# HumidityMetter_v2.net
KiCad netlist of a schematic drawn in EAGLE
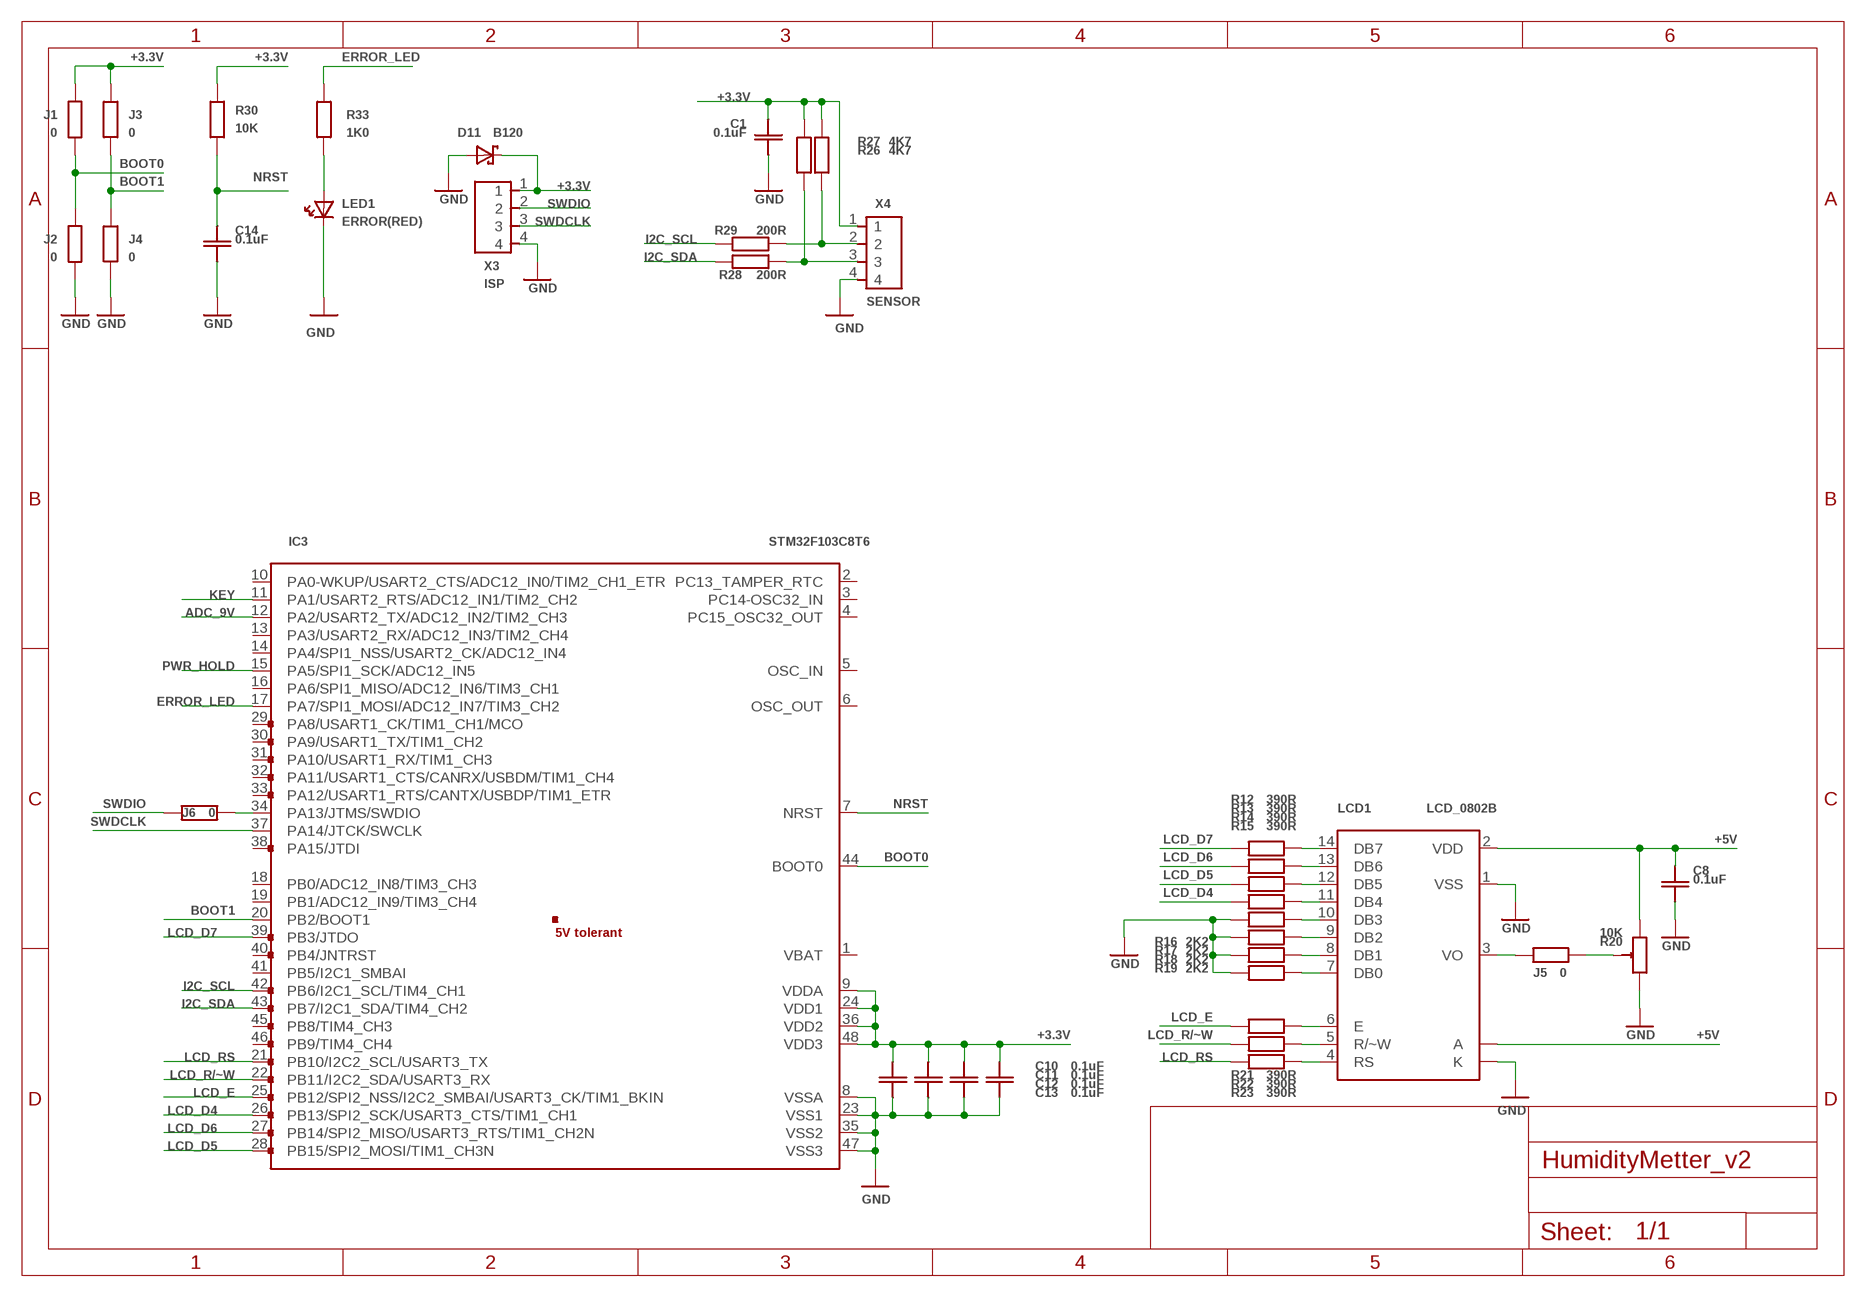
[diagram p0: schematic, sheet 1, part 1 of 2]
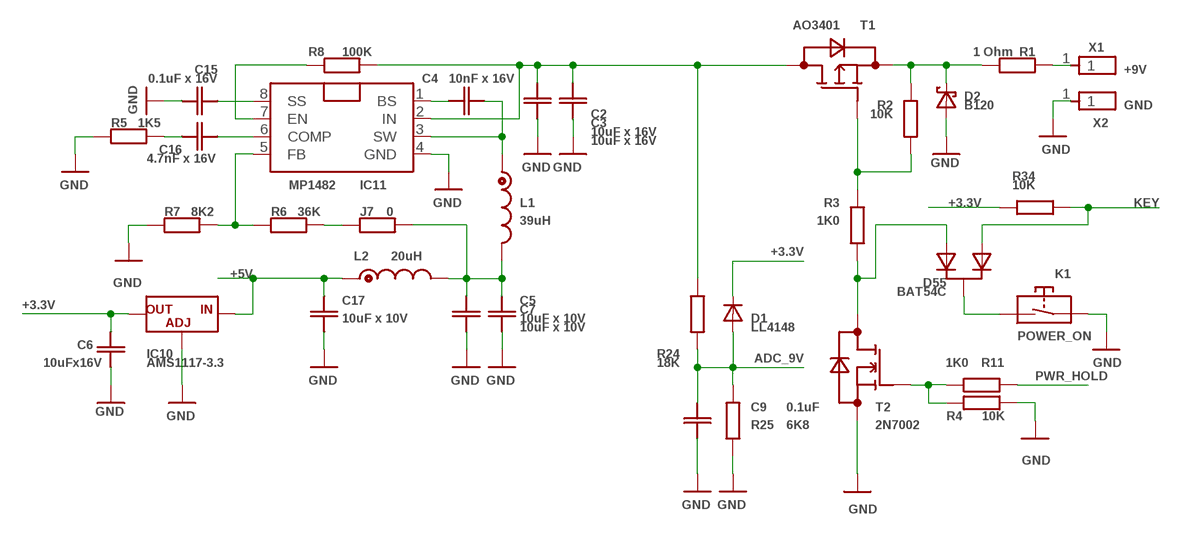
[diagram p1: schematic, sheet 1, part 2 of 2]

(export (version "E")
  (design (tool "Eeschema 10.0.6"))
  (components
    (comp (ref "C1")
      (value "0.1uF")
      (footprint "eagle-import:RSMD_0603")
      (libsource (lib "eagle-import") (part "CSMD_0603"))
    )
    (comp (ref "C2")
      (value "10uF x 16V")
      (footprint "eagle-import:RSMD_1206")
      (libsource (lib "eagle-import") (part "CSMD_1206"))
    )
    (comp (ref "C3")
      (value "10uF x 16V")
      (footprint "eagle-import:RSMD_1206")
      (libsource (lib "eagle-import") (part "CSMD_1206"))
    )
    (comp (ref "C4")
      (value "10nF x 16V")
      (footprint "eagle-import:RSMD_0603")
      (libsource (lib "eagle-import") (part "CSMD_0603"))
    )
    (comp (ref "C5")
      (value "10uF x 10V")
      (footprint "eagle-import:RSMD_1206")
      (libsource (lib "eagle-import") (part "CSMD_1206"))
    )
    (comp (ref "C6")
      (value "10uFx16V")
      (footprint "eagle-import:RSMD_1206")
      (libsource (lib "eagle-import") (part "CSMD_1206"))
    )
    (comp (ref "C7")
      (value "10uF x 10V")
      (footprint "eagle-import:RSMD_1206")
      (libsource (lib "eagle-import") (part "CSMD_1206"))
    )
    (comp (ref "C8")
      (value "0.1uF")
      (footprint "eagle-import:RSMD_0603")
      (libsource (lib "eagle-import") (part "CSMD_0603"))
    )
    (comp (ref "C9")
      (value "0.1uF")
      (footprint "eagle-import:RSMD_0603")
      (libsource (lib "eagle-import") (part "CSMD_0603"))
    )
    (comp (ref "C10")
      (value "0.1uF")
      (footprint "eagle-import:RSMD_0603")
      (libsource (lib "eagle-import") (part "CSMD_0603"))
    )
    (comp (ref "C11")
      (value "0.1uF")
      (footprint "eagle-import:RSMD_0603")
      (libsource (lib "eagle-import") (part "CSMD_0603"))
    )
    (comp (ref "C12")
      (value "0.1uF")
      (footprint "eagle-import:RSMD_0603")
      (libsource (lib "eagle-import") (part "CSMD_0603"))
    )
    (comp (ref "C13")
      (value "0.1uF")
      (footprint "eagle-import:RSMD_0603")
      (libsource (lib "eagle-import") (part "CSMD_0603"))
    )
    (comp (ref "C14")
      (value "0.1uF")
      (footprint "eagle-import:RSMD_0603")
      (libsource (lib "eagle-import") (part "CSMD_0603"))
    )
    (comp (ref "C15")
      (value "0.1uF x 16V")
      (footprint "eagle-import:RSMD_0603")
      (libsource (lib "eagle-import") (part "CSMD_0603"))
    )
    (comp (ref "C16")
      (value "4.7nF x 16V")
      (footprint "eagle-import:RSMD_0603")
      (libsource (lib "eagle-import") (part "CSMD_0603"))
    )
    (comp (ref "C17")
      (value "10uF x 10V")
      (footprint "eagle-import:RSMD_1206")
      (libsource (lib "eagle-import") (part "CSMD_1206"))
    )
    (comp (ref "D1")
      (value "LL4148")
      (footprint "eagle-import:SOD-80")
      (libsource (lib "eagle-import") (part "LL4147SOD-80"))
    )
    (comp (ref "D2")
      (value "B120")
      (footprint "eagle-import:DO-214AC")
      (libsource (lib "eagle-import") (part "B120(DO-214AC)"))
    )
    (comp (ref "D11")
      (value "B120")
      (footprint "eagle-import:DO-214AC")
      (libsource (lib "eagle-import") (part "B120(DO-214AC)"))
    )
    (comp (ref "D55")
      (value "BAT54C")
      (footprint "eagle-import:SOT23_SMALL_PADS")
      (libsource (lib "eagle-import") (part "BAT54C(SOT23)"))
    )
    (comp (ref "IC3")
      (value "STM32F103C8T6")
      (footprint "eagle-import:LQFP48")
      (libsource (lib "eagle-import") (part "STM32F103C8T6(LQFP48)(LQFP48)"))
    )
    (comp (ref "IC10")
      (value "AMS1117-3.3")
      (footprint "eagle-import:SOT223(WAVE_SOLDERING)")
      (libsource (lib "eagle-import") (part "AMS1117SOT223_WS"))
    )
    (comp (ref "IC11")
      (value "MP1482")
      (footprint "eagle-import:SOIC8")
      (libsource (lib "eagle-import") (part "MP1482(SO-8)"))
    )
    (comp (ref "J1")
      (value "0")
      (footprint "eagle-import:RSMD_0603")
      (libsource (lib "eagle-import") (part "RSMD_0603"))
    )
    (comp (ref "J2")
      (value "0")
      (footprint "eagle-import:RSMD_0603")
      (libsource (lib "eagle-import") (part "RSMD_0603"))
    )
    (comp (ref "J3")
      (value "0")
      (footprint "eagle-import:RSMD_0603")
      (libsource (lib "eagle-import") (part "RSMD_0603"))
    )
    (comp (ref "J4")
      (value "0")
      (footprint "eagle-import:RSMD_0603")
      (libsource (lib "eagle-import") (part "RSMD_0603"))
    )
    (comp (ref "J5")
      (value "0")
      (footprint "eagle-import:RSMD_1206_BIG_GAP")
      (libsource (lib "eagle-import") (part "RSMD_1206_BIG_GAP"))
    )
    (comp (ref "J6")
      (value "0")
      (footprint "eagle-import:RSMD_0805")
      (libsource (lib "eagle-import") (part "RSMD_0805"))
    )
    (comp (ref "J7")
      (value "0")
      (footprint "eagle-import:RSMD_1206_BIG_GAP")
      (libsource (lib "eagle-import") (part "RSMD_1206_BIG_GAP"))
    )
    (comp (ref "K1")
      (value "POWER_ON")
      (footprint "eagle-import:KEY_7X4.5")
      (libsource (lib "eagle-import") (part "KEY(7X4.5)"))
    )
    (comp (ref "L1")
      (value "39uH")
      (footprint "eagle-import:COIL_7MM")
      (libsource (lib "eagle-import") (part "L(7MM)"))
    )
    (comp (ref "L2")
      (value "20uH")
      (footprint "eagle-import:RSMD_1206")
      (libsource (lib "eagle-import") (part "L(1206)"))
    )
    (comp (ref "LCD1")
      (value "LCD_0802B")
      (footprint "eagle-import:LCD_0802B_2SCREW(CHINA_CLONE)")
      (libsource (lib "eagle-import") (part "LCD_0802BLCD_0802B_2SCREW(CHINA_CLONE)"))
    )
    (comp (ref "LED1")
      (value "ERROR(RED)")
      (footprint "eagle-import:LED_0805")
      (libsource (lib "eagle-import") (part "LED3MM(SMD0805)"))
    )
    (comp (ref "R1")
      (value "1 Ohm")
      (footprint "eagle-import:RSMD_1206")
      (libsource (lib "eagle-import") (part "RSMD_1206"))
    )
    (comp (ref "R2")
      (value "10K")
      (footprint "eagle-import:RSMD_0603")
      (libsource (lib "eagle-import") (part "RSMD_0603"))
    )
    (comp (ref "R3")
      (value "1K0")
      (footprint "eagle-import:RSMD_0603")
      (libsource (lib "eagle-import") (part "RSMD_0603"))
    )
    (comp (ref "R4")
      (value "10K")
      (footprint "eagle-import:RSMD_0603")
      (libsource (lib "eagle-import") (part "RSMD_0603"))
    )
    (comp (ref "R5")
      (value "1K5")
      (footprint "eagle-import:RSMD_0603")
      (libsource (lib "eagle-import") (part "RSMD_0603"))
    )
    (comp (ref "R6")
      (value "36K")
      (footprint "eagle-import:RSMD_0603")
      (libsource (lib "eagle-import") (part "RSMD_0603"))
    )
    (comp (ref "R7")
      (value "8K2")
      (footprint "eagle-import:RSMD_0603")
      (libsource (lib "eagle-import") (part "RSMD_0603"))
    )
    (comp (ref "R8")
      (value "100K")
      (footprint "eagle-import:RSMD_0603")
      (libsource (lib "eagle-import") (part "RSMD_0603"))
    )
    (comp (ref "R11")
      (value "1K0")
      (footprint "eagle-import:RSMD_0603")
      (libsource (lib "eagle-import") (part "RSMD_0603"))
    )
    (comp (ref "R12")
      (value "390R")
      (footprint "eagle-import:RSMD_0805")
      (libsource (lib "eagle-import") (part "RSMD_0805"))
    )
    (comp (ref "R13")
      (value "390R")
      (footprint "eagle-import:RSMD_0603")
      (libsource (lib "eagle-import") (part "RSMD_0603"))
    )
    (comp (ref "R14")
      (value "390R")
      (footprint "eagle-import:RSMD_0603")
      (libsource (lib "eagle-import") (part "RSMD_0603"))
    )
    (comp (ref "R15")
      (value "390R")
      (footprint "eagle-import:RSMD_0603")
      (libsource (lib "eagle-import") (part "RSMD_0603"))
    )
    (comp (ref "R16")
      (value "2K2")
      (footprint "eagle-import:RSMD_0603")
      (libsource (lib "eagle-import") (part "RSMD_0603"))
    )
    (comp (ref "R17")
      (value "2K2")
      (footprint "eagle-import:RSMD_0603")
      (libsource (lib "eagle-import") (part "RSMD_0603"))
    )
    (comp (ref "R18")
      (value "2K2")
      (footprint "eagle-import:RSMD_0603")
      (libsource (lib "eagle-import") (part "RSMD_0603"))
    )
    (comp (ref "R19")
      (value "2K2")
      (footprint "eagle-import:RSMD_0603")
      (libsource (lib "eagle-import") (part "RSMD_0603"))
    )
    (comp (ref "R20")
      (value "10K")
      (footprint "eagle-import:R_ADJ_HOR")
      (libsource (lib "eagle-import") (part "R_ADJHOR_7X7MM"))
    )
    (comp (ref "R21")
      (value "390R")
      (footprint "eagle-import:RSMD_0603")
      (libsource (lib "eagle-import") (part "RSMD_0603"))
    )
    (comp (ref "R22")
      (value "390R")
      (footprint "eagle-import:RSMD_0603")
      (libsource (lib "eagle-import") (part "RSMD_0603"))
    )
    (comp (ref "R23")
      (value "390R")
      (footprint "eagle-import:RSMD_0603")
      (libsource (lib "eagle-import") (part "RSMD_0603"))
    )
    (comp (ref "R24")
      (value "18K")
      (footprint "eagle-import:RSMD_0603")
      (libsource (lib "eagle-import") (part "RSMD_0603"))
    )
    (comp (ref "R25")
      (value "6K8")
      (footprint "eagle-import:RSMD_0603")
      (libsource (lib "eagle-import") (part "RSMD_0603"))
    )
    (comp (ref "R26")
      (value "4K7")
      (footprint "eagle-import:RSMD_0603")
      (libsource (lib "eagle-import") (part "RSMD_0603"))
    )
    (comp (ref "R27")
      (value "4K7")
      (footprint "eagle-import:RSMD_0603")
      (libsource (lib "eagle-import") (part "RSMD_0603"))
    )
    (comp (ref "R28")
      (value "200R")
      (footprint "eagle-import:RSMD_0603")
      (libsource (lib "eagle-import") (part "RSMD_0603"))
    )
    (comp (ref "R29")
      (value "200R")
      (footprint "eagle-import:RSMD_0603")
      (libsource (lib "eagle-import") (part "RSMD_0603"))
    )
    (comp (ref "R30")
      (value "10K")
      (footprint "eagle-import:RSMD_0603")
      (libsource (lib "eagle-import") (part "RSMD_0603"))
    )
    (comp (ref "R33")
      (value "1K0")
      (footprint "eagle-import:RSMD_0603")
      (libsource (lib "eagle-import") (part "RSMD_0603"))
    )
    (comp (ref "R34")
      (value "10K")
      (footprint "eagle-import:RSMD_0603")
      (libsource (lib "eagle-import") (part "RSMD_0603"))
    )
    (comp (ref "T1")
      (value "AO3401")
      (footprint "eagle-import:SOT23")
      (libsource (lib "eagle-import") (part "BSS84(SOT23)"))
    )
    (comp (ref "T2")
      (value "2N7002")
      (footprint "eagle-import:SOT23_SMALL_PADS")
      (libsource (lib "eagle-import") (part "2N7002SOT23_SMALL_PADS"))
    )
    (comp (ref "X1")
      (value "+9V")
      (footprint "eagle-import:PIN1X1_3.5MM_PWR")
      (libsource (lib "eagle-import") (part "PIN1X13.5MM_PWR"))
    )
    (comp (ref "X2")
      (value "GND")
      (footprint "eagle-import:PIN1X1_3.5MM_PWR")
      (libsource (lib "eagle-import") (part "PIN1X13.5MM_PWR"))
    )
    (comp (ref "X3")
      (value "ISP")
      (footprint "eagle-import:PIN4X1_2.54MM")
      (libsource (lib "eagle-import") (part "PIN4X1(2.54MM)"))
    )
    (comp (ref "X4")
      (value "SENSOR")
      (footprint "eagle-import:JST_XH2.5MM_4PIN")
      (libsource (lib "eagle-import") (part "PIN4X1(JST_XH2.5)"))
    )
  )
  (nets
    (net (code "1") (name "/+3.3V") (class "Default")
      (node (ref "C1") (pin "PAD_1") (pinfunction "PIN1_PAD_1") (pintype "bidirectional"))
      (node (ref "C10") (pin "PAD_1") (pinfunction "PIN1_PAD_1") (pintype "bidirectional"))
      (node (ref "C11") (pin "PAD_1") (pinfunction "PIN1_PAD_1") (pintype "bidirectional"))
      (node (ref "C12") (pin "PAD_1") (pinfunction "PIN1_PAD_1") (pintype "bidirectional"))
      (node (ref "C13") (pin "PAD_1") (pinfunction "PIN1_PAD_1") (pintype "bidirectional"))
      (node (ref "C6") (pin "PAD_1") (pinfunction "PIN1_PAD_1") (pintype "bidirectional"))
      (node (ref "D1") (pin "CATHODE") (pinfunction "CATHODE_CATHODE") (pintype "passive"))
      (node (ref "D11") (pin "CATHODE") (pinfunction "CATHODE_CATHODE") (pintype "passive"))
      (node (ref "IC10") (pin "2") (pinfunction "OUT_2") (pintype "output"))
      (node (ref "IC10") (pin "4") (pinfunction "OUT_4") (pintype "output"))
      (node (ref "IC3") (pin "24") (pinfunction "VDD1_24") (pintype "bidirectional"))
      (node (ref "IC3") (pin "36") (pinfunction "VDD2_36") (pintype "bidirectional"))
      (node (ref "IC3") (pin "48") (pinfunction "VDD3_48") (pintype "bidirectional"))
      (node (ref "IC3") (pin "9") (pinfunction "VDDA_9") (pintype "bidirectional"))
      (node (ref "J1") (pin "PAD_0") (pinfunction "PIN0_PAD_0") (pintype "passive"))
      (node (ref "J3") (pin "PAD_0") (pinfunction "PIN0_PAD_0") (pintype "passive"))
      (node (ref "R26") (pin "PAD_0") (pinfunction "PIN0_PAD_0") (pintype "passive"))
      (node (ref "R27") (pin "PAD_0") (pinfunction "PIN0_PAD_0") (pintype "passive"))
      (node (ref "R30") (pin "PAD_0") (pinfunction "PIN0_PAD_0") (pintype "passive"))
      (node (ref "R34") (pin "PAD_0") (pinfunction "PIN0_PAD_0") (pintype "passive"))
      (node (ref "X3") (pin "1") (pinfunction "1_1") (pintype "bidirectional"))
      (node (ref "X4") (pin "1") (pinfunction "1_1") (pintype "bidirectional"))
    )
    (net (code "2") (name "/+5V") (class "Default")
      (node (ref "C17") (pin "PAD_1") (pinfunction "PIN1_PAD_1") (pintype "bidirectional"))
      (node (ref "C8") (pin "PAD_1") (pinfunction "PIN1_PAD_1") (pintype "bidirectional"))
      (node (ref "IC10") (pin "3") (pinfunction "IN_3") (pintype "input"))
      (node (ref "L2") (pin "PAD_1") (pinfunction "START_PAD_1") (pintype "bidirectional"))
      (node (ref "LCD1") (pin "2") (pinfunction "VDD_2") (pintype "bidirectional"))
      (node (ref "LCD1") (pin "A") (pinfunction "A_A") (pintype "bidirectional"))
      (node (ref "R20") (pin "1") (pinfunction "END_A_1") (pintype "passive"))
    )
    (net (code "3") (name "/ADC_9V") (class "Default")
      (node (ref "C9") (pin "PAD_1") (pinfunction "PIN1_PAD_1") (pintype "bidirectional"))
      (node (ref "D1") (pin "ANODE") (pinfunction "ANODE_ANODE") (pintype "passive"))
      (node (ref "IC3") (pin "12") (pinfunction "PA2/USART2_TX/ADC12_IN2/TIM2_CH3_12") (pintype "bidirectional"))
      (node (ref "R24") (pin "PAD_1") (pinfunction "PIN1_PAD_1") (pintype "passive"))
      (node (ref "R25") (pin "PAD_0") (pinfunction "PIN0_PAD_0") (pintype "passive"))
    )
    (net (code "4") (name "/BOOT0") (class "Default")
      (node (ref "IC3") (pin "44") (pinfunction "BOOT0_44") (pintype "bidirectional"))
      (node (ref "J1") (pin "PAD_1") (pinfunction "PIN1_PAD_1") (pintype "passive"))
      (node (ref "J2") (pin "PAD_0") (pinfunction "PIN0_PAD_0") (pintype "passive"))
    )
    (net (code "5") (name "/BOOT1") (class "Default")
      (node (ref "IC3") (pin "20") (pinfunction "PB2/BOOT1_20") (pintype "bidirectional"))
      (node (ref "J3") (pin "PAD_1") (pinfunction "PIN1_PAD_1") (pintype "passive"))
      (node (ref "J4") (pin "PAD_0") (pinfunction "PIN0_PAD_0") (pintype "passive"))
    )
    (net (code "6") (name "/ERROR_LED") (class "Default")
      (node (ref "IC3") (pin "17") (pinfunction "PA7/SPI1_MOSI/ADC12_IN7/TIM3_CH2_17") (pintype "bidirectional"))
      (node (ref "R33") (pin "PAD_0") (pinfunction "PIN0_PAD_0") (pintype "passive"))
    )
    (net (code "7") (name "/I2C_SCL") (class "Default")
      (node (ref "IC3") (pin "42") (pinfunction "PB6/I2C1_SCL/TIM4_CH1_42") (pintype "bidirectional"))
      (node (ref "R29") (pin "PAD_0") (pinfunction "PIN0_PAD_0") (pintype "passive"))
    )
    (net (code "8") (name "/I2C_SDA") (class "Default")
      (node (ref "IC3") (pin "43") (pinfunction "PB7/I2C1_SDA/TIM4_CH2_43") (pintype "bidirectional"))
      (node (ref "R28") (pin "PAD_0") (pinfunction "PIN0_PAD_0") (pintype "passive"))
    )
    (net (code "9") (name "/KEY") (class "Default")
      (node (ref "D55") (pin "2") (pinfunction "ANODE2_2") (pintype "passive"))
      (node (ref "IC3") (pin "11") (pinfunction "PA1/USART2_RTS/ADC12_IN1/TIM2_CH2_11") (pintype "bidirectional"))
      (node (ref "R34") (pin "PAD_1") (pinfunction "PIN1_PAD_1") (pintype "passive"))
    )
    (net (code "10") (name "/LCD_D4") (class "Default")
      (node (ref "IC3") (pin "26") (pinfunction "PB13/SPI2_SCK/USART3_CTS/TIM1_CH1_26") (pintype "bidirectional"))
      (node (ref "R15") (pin "PAD_1") (pinfunction "PIN1_PAD_1") (pintype "passive"))
    )
    (net (code "11") (name "/LCD_D5") (class "Default")
      (node (ref "IC3") (pin "28") (pinfunction "PB15/SPI2_MOSI/TIM1_CH3N_28") (pintype "bidirectional"))
      (node (ref "R14") (pin "PAD_1") (pinfunction "PIN1_PAD_1") (pintype "passive"))
    )
    (net (code "12") (name "/LCD_D6") (class "Default")
      (node (ref "IC3") (pin "27") (pinfunction "PB14/SPI2_MISO/USART3_RTS/TIM1_CH2N_27") (pintype "bidirectional"))
      (node (ref "R13") (pin "PAD_1") (pinfunction "PIN1_PAD_1") (pintype "passive"))
    )
    (net (code "13") (name "/LCD_D7") (class "Default")
      (node (ref "IC3") (pin "39") (pinfunction "PB3/JTDO_39") (pintype "bidirectional"))
      (node (ref "R12") (pin "PAD_1") (pinfunction "PIN1_PAD_1") (pintype "passive"))
    )
    (net (code "14") (name "/LCD_E") (class "Default")
      (node (ref "IC3") (pin "25") (pinfunction "PB12/SPI2_NSS/I2C2_SMBAI/USART3_CK/TIM1_BKIN_25") (pintype "bidirectional"))
      (node (ref "R21") (pin "PAD_1") (pinfunction "PIN1_PAD_1") (pintype "passive"))
    )
    (net (code "15") (name "/LCD_RS") (class "Default")
      (node (ref "IC3") (pin "21") (pinfunction "PB10/I2C2_SCL/USART3_TX_21") (pintype "bidirectional"))
      (node (ref "R23") (pin "PAD_1") (pinfunction "PIN1_PAD_1") (pintype "passive"))
    )
    (net (code "16") (name "/LCD_R{slash}~{W}") (class "Default")
      (node (ref "IC3") (pin "22") (pinfunction "PB11/I2C2_SDA/USART3_RX_22") (pintype "bidirectional"))
      (node (ref "R22") (pin "PAD_1") (pinfunction "PIN1_PAD_1") (pintype "passive"))
    )
    (net (code "17") (name "/NRST") (class "Default")
      (node (ref "C14") (pin "PAD_1") (pinfunction "PIN1_PAD_1") (pintype "bidirectional"))
      (node (ref "IC3") (pin "7") (pinfunction "NRST_7") (pintype "bidirectional"))
      (node (ref "R30") (pin "PAD_1") (pinfunction "PIN1_PAD_1") (pintype "passive"))
    )
    (net (code "18") (name "/PWR_HOLD") (class "Default")
      (node (ref "IC3") (pin "15") (pinfunction "PA5/SPI1_SCK/ADC12_IN5_15") (pintype "bidirectional"))
      (node (ref "R11") (pin "PAD_0") (pinfunction "PIN0_PAD_0") (pintype "passive"))
    )
    (net (code "19") (name "/SWDCLK") (class "Default")
      (node (ref "IC3") (pin "37") (pinfunction "PA14/JTCK/SWCLK_37") (pintype "bidirectional"))
      (node (ref "X3") (pin "3") (pinfunction "3_3") (pintype "bidirectional"))
    )
    (net (code "20") (name "/SWDIO") (class "Default")
      (node (ref "J6") (pin "PAD_1") (pinfunction "PIN1_PAD_1") (pintype "passive"))
      (node (ref "X3") (pin "2") (pinfunction "2_2") (pintype "bidirectional"))
    )
    (net (code "21") (name "GND") (class "Default")
      (node (ref "C1") (pin "PAD_0") (pinfunction "PIN0_PAD_0") (pintype "bidirectional"))
      (node (ref "C10") (pin "PAD_0") (pinfunction "PIN0_PAD_0") (pintype "bidirectional"))
      (node (ref "C11") (pin "PAD_0") (pinfunction "PIN0_PAD_0") (pintype "bidirectional"))
      (node (ref "C12") (pin "PAD_0") (pinfunction "PIN0_PAD_0") (pintype "bidirectional"))
      (node (ref "C13") (pin "PAD_0") (pinfunction "PIN0_PAD_0") (pintype "bidirectional"))
      (node (ref "C14") (pin "PAD_0") (pinfunction "PIN0_PAD_0") (pintype "bidirectional"))
      (node (ref "C15") (pin "PAD_0") (pinfunction "PIN0_PAD_0") (pintype "bidirectional"))
      (node (ref "C17") (pin "PAD_0") (pinfunction "PIN0_PAD_0") (pintype "bidirectional"))
      (node (ref "C2") (pin "PAD_0") (pinfunction "PIN0_PAD_0") (pintype "bidirectional"))
      (node (ref "C3") (pin "PAD_0") (pinfunction "PIN0_PAD_0") (pintype "bidirectional"))
      (node (ref "C5") (pin "PAD_0") (pinfunction "PIN0_PAD_0") (pintype "bidirectional"))
      (node (ref "C6") (pin "PAD_0") (pinfunction "PIN0_PAD_0") (pintype "bidirectional"))
      (node (ref "C7") (pin "PAD_0") (pinfunction "PIN0_PAD_0") (pintype "bidirectional"))
      (node (ref "C8") (pin "PAD_0") (pinfunction "PIN0_PAD_0") (pintype "bidirectional"))
      (node (ref "C9") (pin "PAD_0") (pinfunction "PIN0_PAD_0") (pintype "bidirectional"))
      (node (ref "D11") (pin "ANODE") (pinfunction "ANODE_ANODE") (pintype "passive"))
      (node (ref "D2") (pin "ANODE") (pinfunction "ANODE_ANODE") (pintype "passive"))
      (node (ref "IC10") (pin "1") (pinfunction "ADJ_1") (pintype "input"))
      (node (ref "IC11") (pin "4") (pinfunction "GND_4") (pintype "bidirectional"))
      (node (ref "IC3") (pin "23") (pinfunction "VSS1_23") (pintype "bidirectional"))
      (node (ref "IC3") (pin "35") (pinfunction "VSS2_35") (pintype "bidirectional"))
      (node (ref "IC3") (pin "47") (pinfunction "VSS3_47") (pintype "bidirectional"))
      (node (ref "IC3") (pin "8") (pinfunction "VSSA_8") (pintype "bidirectional"))
      (node (ref "J2") (pin "PAD_1") (pinfunction "PIN1_PAD_1") (pintype "passive"))
      (node (ref "J4") (pin "PAD_1") (pinfunction "PIN1_PAD_1") (pintype "passive"))
      (node (ref "K1") (pin "1") (pinfunction "1_1") (pintype "bidirectional"))
      (node (ref "K1") (pin "2") (pinfunction "1_2") (pintype "bidirectional"))
      (node (ref "LCD1") (pin "1") (pinfunction "VSS_1") (pintype "bidirectional"))
      (node (ref "LCD1") (pin "K") (pinfunction "K_K") (pintype "bidirectional"))
      (node (ref "LED1") (pin "CATHODE") (pinfunction "CATHODE_CATHODE") (pintype "passive"))
      (node (ref "R16") (pin "PAD_1") (pinfunction "PIN1_PAD_1") (pintype "passive"))
      (node (ref "R17") (pin "PAD_1") (pinfunction "PIN1_PAD_1") (pintype "passive"))
      (node (ref "R18") (pin "PAD_1") (pinfunction "PIN1_PAD_1") (pintype "passive"))
      (node (ref "R19") (pin "PAD_1") (pinfunction "PIN1_PAD_1") (pintype "passive"))
      (node (ref "R20") (pin "3") (pinfunction "END_B_3") (pintype "passive"))
      (node (ref "R25") (pin "PAD_1") (pinfunction "PIN1_PAD_1") (pintype "passive"))
      (node (ref "R4") (pin "PAD_1") (pinfunction "PIN1_PAD_1") (pintype "passive"))
      (node (ref "R5") (pin "PAD_1") (pinfunction "PIN1_PAD_1") (pintype "passive"))
      (node (ref "R7") (pin "PAD_1") (pinfunction "PIN1_PAD_1") (pintype "passive"))
      (node (ref "T2") (pin "2") (pinfunction "SOURCE_2") (pintype "bidirectional"))
      (node (ref "X2") (pin "1") (pinfunction "1_1") (pintype "bidirectional"))
      (node (ref "X3") (pin "4") (pinfunction "4_4") (pintype "bidirectional"))
      (node (ref "X4") (pin "4") (pinfunction "4_4") (pintype "bidirectional"))
    )
    (net (code "22") (name "Net-(C2-PIN1)") (class "Default")
      (node (ref "C2") (pin "PAD_1") (pinfunction "PIN1_PAD_1") (pintype "bidirectional"))
      (node (ref "C3") (pin "PAD_1") (pinfunction "PIN1_PAD_1") (pintype "bidirectional"))
      (node (ref "IC11") (pin "2") (pinfunction "IN_2") (pintype "bidirectional"))
      (node (ref "R24") (pin "PAD_0") (pinfunction "PIN0_PAD_0") (pintype "passive"))
      (node (ref "R8") (pin "PAD_1") (pinfunction "PIN1_PAD_1") (pintype "passive"))
      (node (ref "T1") (pin "3") (pinfunction "DRAIN_3") (pintype "bidirectional"))
    )
    (net (code "23") (name "Net-(C4-PIN0)") (class "Default")
      (node (ref "C4") (pin "PAD_0") (pinfunction "PIN0_PAD_0") (pintype "bidirectional"))
      (node (ref "IC11") (pin "3") (pinfunction "SW_3") (pintype "bidirectional"))
      (node (ref "L1") (pin "1") (pinfunction "START_1") (pintype "bidirectional"))
    )
    (net (code "24") (name "Net-(C4-PIN1)") (class "Default")
      (node (ref "C4") (pin "PAD_1") (pinfunction "PIN1_PAD_1") (pintype "bidirectional"))
      (node (ref "IC11") (pin "1") (pinfunction "BS_1") (pintype "bidirectional"))
    )
    (net (code "25") (name "Net-(C5-PIN1)") (class "Default")
      (node (ref "C5") (pin "PAD_1") (pinfunction "PIN1_PAD_1") (pintype "bidirectional"))
      (node (ref "C7") (pin "PAD_1") (pinfunction "PIN1_PAD_1") (pintype "bidirectional"))
      (node (ref "J7") (pin "PAD_0") (pinfunction "PIN0_PAD_0") (pintype "passive"))
      (node (ref "L1") (pin "2") (pinfunction "END_2") (pintype "bidirectional"))
      (node (ref "L2") (pin "PAD_0") (pinfunction "END_PAD_0") (pintype "bidirectional"))
    )
    (net (code "26") (name "Net-(C15-PIN1)") (class "Default")
      (node (ref "C15") (pin "PAD_1") (pinfunction "PIN1_PAD_1") (pintype "bidirectional"))
      (node (ref "IC11") (pin "8") (pinfunction "SS_8") (pintype "bidirectional"))
    )
    (net (code "27") (name "Net-(C16-PIN0)") (class "Default")
      (node (ref "C16") (pin "PAD_0") (pinfunction "PIN0_PAD_0") (pintype "bidirectional"))
      (node (ref "R5") (pin "PAD_0") (pinfunction "PIN0_PAD_0") (pintype "passive"))
    )
    (net (code "28") (name "Net-(C16-PIN1)") (class "Default")
      (node (ref "C16") (pin "PAD_1") (pinfunction "PIN1_PAD_1") (pintype "bidirectional"))
      (node (ref "IC11") (pin "6") (pinfunction "COMP_6") (pintype "bidirectional"))
    )
    (net (code "29") (name "Net-(D55-ANODE1)") (class "Default")
      (node (ref "D55") (pin "1") (pinfunction "ANODE1_1") (pintype "passive"))
      (node (ref "R3") (pin "PAD_1") (pinfunction "PIN1_PAD_1") (pintype "passive"))
      (node (ref "T2") (pin "3") (pinfunction "DRAIN_3") (pintype "bidirectional"))
    )
    (net (code "30") (name "Net-(D55-CATHODE)") (class "Default")
      (node (ref "D55") (pin "3") (pinfunction "CATHODE_3") (pintype "passive"))
      (node (ref "K1") (pin "3") (pinfunction "2_3") (pintype "bidirectional"))
      (node (ref "K1") (pin "4") (pinfunction "2_4") (pintype "bidirectional"))
    )
    (net (code "31") (name "Net-(IC3-PA13{slash}JTMS{slash}SWDIO)") (class "Default")
      (node (ref "IC3") (pin "34") (pinfunction "PA13/JTMS/SWDIO_34") (pintype "bidirectional"))
      (node (ref "J6") (pin "PAD_0") (pinfunction "PIN0_PAD_0") (pintype "passive"))
    )
    (net (code "32") (name "Net-(IC11-EN)") (class "Default")
      (node (ref "IC11") (pin "7") (pinfunction "EN_7") (pintype "bidirectional"))
      (node (ref "R8") (pin "PAD_0") (pinfunction "PIN0_PAD_0") (pintype "passive"))
    )
    (net (code "33") (name "Net-(IC11-FB)") (class "Default")
      (node (ref "IC11") (pin "5") (pinfunction "FB_5") (pintype "bidirectional"))
      (node (ref "R6") (pin "PAD_1") (pinfunction "PIN1_PAD_1") (pintype "passive"))
      (node (ref "R7") (pin "PAD_0") (pinfunction "PIN0_PAD_0") (pintype "passive"))
    )
    (net (code "34") (name "Net-(J5-PIN0)") (class "Default")
      (node (ref "J5") (pin "PAD_0") (pinfunction "PIN0_PAD_0") (pintype "passive"))
      (node (ref "R20") (pin "2") (pinfunction "ADJ_2") (pintype "passive"))
    )
    (net (code "35") (name "Net-(J5-PIN1)") (class "Default")
      (node (ref "J5") (pin "PAD_1") (pinfunction "PIN1_PAD_1") (pintype "passive"))
      (node (ref "LCD1") (pin "3") (pinfunction "VO_3") (pintype "bidirectional"))
    )
    (net (code "36") (name "Net-(J7-PIN1)") (class "Default")
      (node (ref "J7") (pin "PAD_1") (pinfunction "PIN1_PAD_1") (pintype "passive"))
      (node (ref "R6") (pin "PAD_0") (pinfunction "PIN0_PAD_0") (pintype "passive"))
    )
    (net (code "37") (name "Net-(LCD1-DB0)") (class "Default")
      (node (ref "LCD1") (pin "7") (pinfunction "DB0_7") (pintype "bidirectional"))
      (node (ref "R19") (pin "PAD_0") (pinfunction "PIN0_PAD_0") (pintype "passive"))
    )
    (net (code "38") (name "Net-(LCD1-DB1)") (class "Default")
      (node (ref "LCD1") (pin "8") (pinfunction "DB1_8") (pintype "bidirectional"))
      (node (ref "R18") (pin "PAD_0") (pinfunction "PIN0_PAD_0") (pintype "passive"))
    )
    (net (code "39") (name "Net-(LCD1-DB2)") (class "Default")
      (node (ref "LCD1") (pin "9") (pinfunction "DB2_9") (pintype "bidirectional"))
      (node (ref "R17") (pin "PAD_0") (pinfunction "PIN0_PAD_0") (pintype "passive"))
    )
    (net (code "40") (name "Net-(LCD1-DB3)") (class "Default")
      (node (ref "LCD1") (pin "10") (pinfunction "DB3_10") (pintype "bidirectional"))
      (node (ref "R16") (pin "PAD_0") (pinfunction "PIN0_PAD_0") (pintype "passive"))
    )
    (net (code "41") (name "Net-(LCD1-DB4)") (class "Default")
      (node (ref "LCD1") (pin "11") (pinfunction "DB4_11") (pintype "bidirectional"))
      (node (ref "R15") (pin "PAD_0") (pinfunction "PIN0_PAD_0") (pintype "passive"))
    )
    (net (code "42") (name "Net-(LCD1-DB5)") (class "Default")
      (node (ref "LCD1") (pin "12") (pinfunction "DB5_12") (pintype "bidirectional"))
      (node (ref "R14") (pin "PAD_0") (pinfunction "PIN0_PAD_0") (pintype "passive"))
    )
    (net (code "43") (name "Net-(LCD1-DB6)") (class "Default")
      (node (ref "LCD1") (pin "13") (pinfunction "DB6_13") (pintype "bidirectional"))
      (node (ref "R13") (pin "PAD_0") (pinfunction "PIN0_PAD_0") (pintype "passive"))
    )
    (net (code "44") (name "Net-(LCD1-DB7)") (class "Default")
      (node (ref "LCD1") (pin "14") (pinfunction "DB7_14") (pintype "bidirectional"))
      (node (ref "R12") (pin "PAD_0") (pinfunction "PIN0_PAD_0") (pintype "passive"))
    )
    (net (code "45") (name "Net-(LCD1-E)") (class "Default")
      (node (ref "LCD1") (pin "6") (pinfunction "E_6") (pintype "bidirectional"))
      (node (ref "R21") (pin "PAD_0") (pinfunction "PIN0_PAD_0") (pintype "passive"))
    )
    (net (code "46") (name "Net-(LCD1-RS)") (class "Default")
      (node (ref "LCD1") (pin "4") (pinfunction "RS_4") (pintype "bidirectional"))
      (node (ref "R23") (pin "PAD_0") (pinfunction "PIN0_PAD_0") (pintype "passive"))
    )
    (net (code "47") (name "Net-(LCD1-R{slash}~{W})") (class "Default")
      (node (ref "LCD1") (pin "5") (pinfunction "R/~{W}_5") (pintype "bidirectional"))
      (node (ref "R22") (pin "PAD_0") (pinfunction "PIN0_PAD_0") (pintype "passive"))
    )
    (net (code "48") (name "Net-(R1-PIN0)") (class "Default")
      (node (ref "D2") (pin "CATHODE") (pinfunction "CATHODE_CATHODE") (pintype "passive"))
      (node (ref "R1") (pin "PAD_0") (pinfunction "PIN0_PAD_0") (pintype "passive"))
      (node (ref "R2") (pin "PAD_0") (pinfunction "PIN0_PAD_0") (pintype "passive"))
      (node (ref "T1") (pin "2") (pinfunction "SOURCE_2") (pintype "bidirectional"))
    )
    (net (code "49") (name "Net-(R1-PIN1)") (class "Default")
      (node (ref "R1") (pin "PAD_1") (pinfunction "PIN1_PAD_1") (pintype "passive"))
      (node (ref "X1") (pin "1") (pinfunction "1_1") (pintype "bidirectional"))
    )
    (net (code "50") (name "Net-(R2-PIN1)") (class "Default")
      (node (ref "R2") (pin "PAD_1") (pinfunction "PIN1_PAD_1") (pintype "passive"))
      (node (ref "R3") (pin "PAD_0") (pinfunction "PIN0_PAD_0") (pintype "passive"))
      (node (ref "T1") (pin "1") (pinfunction "GATE_1") (pintype "bidirectional"))
    )
    (net (code "51") (name "Net-(R11-PIN1)") (class "Default")
      (node (ref "R11") (pin "PAD_1") (pinfunction "PIN1_PAD_1") (pintype "passive"))
      (node (ref "R4") (pin "PAD_0") (pinfunction "PIN0_PAD_0") (pintype "passive"))
      (node (ref "T2") (pin "1") (pinfunction "GATE_1") (pintype "bidirectional"))
    )
    (net (code "52") (name "Net-(R26-PIN1)") (class "Default")
      (node (ref "R26") (pin "PAD_1") (pinfunction "PIN1_PAD_1") (pintype "passive"))
      (node (ref "R29") (pin "PAD_1") (pinfunction "PIN1_PAD_1") (pintype "passive"))
      (node (ref "X4") (pin "2") (pinfunction "2_2") (pintype "bidirectional"))
    )
    (net (code "53") (name "Net-(R27-PIN1)") (class "Default")
      (node (ref "R27") (pin "PAD_1") (pinfunction "PIN1_PAD_1") (pintype "passive"))
      (node (ref "R28") (pin "PAD_1") (pinfunction "PIN1_PAD_1") (pintype "passive"))
      (node (ref "X4") (pin "3") (pinfunction "3_3") (pintype "bidirectional"))
    )
    (net (code "54") (name "Net-(R33-PIN1)") (class "Default")
      (node (ref "LED1") (pin "ANODE") (pinfunction "ANODE_ANODE") (pintype "passive"))
      (node (ref "R33") (pin "PAD_1") (pinfunction "PIN1_PAD_1") (pintype "passive"))
    )
    (net (code "55") (name "unconnected-(IC3-OSC_IN-Pad5)") (class "Default")
      (node (ref "IC3") (pin "5") (pinfunction "OSC_IN_5") (pintype "bidirectional"))
    )
    (net (code "56") (name "unconnected-(IC3-OSC_OUT-Pad6)") (class "Default")
      (node (ref "IC3") (pin "6") (pinfunction "OSC_OUT_6") (pintype "bidirectional"))
    )
    (net (code "57") (name "unconnected-(IC3-PA0-WKUP{slash}USART2_CTS{slash}ADC12_IN0{slash}TIM2_CH1_ETR-Pad10)") (class "Default")
      (node (ref "IC3") (pin "10") (pinfunction "PA0-WKUP/USART2_CTS/ADC12_IN0/TIM2_CH1_ETR_10") (pintype "bidirectional"))
    )
    (net (code "58") (name "unconnected-(IC3-PA3{slash}USART2_RX{slash}ADC12_IN3{slash}TIM2_CH4-Pad13)") (class "Default")
      (node (ref "IC3") (pin "13") (pinfunction "PA3/USART2_RX/ADC12_IN3/TIM2_CH4_13") (pintype "bidirectional"))
    )
    (net (code "59") (name "unconnected-(IC3-PA4{slash}SPI1_NSS{slash}USART2_CK{slash}ADC12_IN4-Pad14)") (class "Default")
      (node (ref "IC3") (pin "14") (pinfunction "PA4/SPI1_NSS/USART2_CK/ADC12_IN4_14") (pintype "bidirectional"))
    )
    (net (code "60") (name "unconnected-(IC3-PA6{slash}SPI1_MISO{slash}ADC12_IN6{slash}TIM3_CH1-Pad16)") (class "Default")
      (node (ref "IC3") (pin "16") (pinfunction "PA6/SPI1_MISO/ADC12_IN6/TIM3_CH1_16") (pintype "bidirectional"))
    )
    (net (code "61") (name "unconnected-(IC3-PA8{slash}USART1_CK{slash}TIM1_CH1{slash}MCO-Pad29)") (class "Default")
      (node (ref "IC3") (pin "29") (pinfunction "PA8/USART1_CK/TIM1_CH1/MCO_29") (pintype "bidirectional"))
    )
    (net (code "62") (name "unconnected-(IC3-PA9{slash}USART1_TX{slash}TIM1_CH2-Pad30)") (class "Default")
      (node (ref "IC3") (pin "30") (pinfunction "PA9/USART1_TX/TIM1_CH2_30") (pintype "bidirectional"))
    )
    (net (code "63") (name "unconnected-(IC3-PA10{slash}USART1_RX{slash}TIM1_CH3-Pad31)") (class "Default")
      (node (ref "IC3") (pin "31") (pinfunction "PA10/USART1_RX/TIM1_CH3_31") (pintype "bidirectional"))
    )
    (net (code "64") (name "unconnected-(IC3-PA11{slash}USART1_CTS{slash}CANRX{slash}USBDM{slash}TIM1_CH4-Pad32)") (class "Default")
      (node (ref "IC3") (pin "32") (pinfunction "PA11/USART1_CTS/CANRX/USBDM/TIM1_CH4_32") (pintype "bidirectional"))
    )
    (net (code "65") (name "unconnected-(IC3-PA12{slash}USART1_RTS{slash}CANTX{slash}USBDP{slash}TIM1_ETR-Pad33)") (class "Default")
      (node (ref "IC3") (pin "33") (pinfunction "PA12/USART1_RTS/CANTX/USBDP/TIM1_ETR_33") (pintype "bidirectional"))
    )
    (net (code "66") (name "unconnected-(IC3-PA15{slash}JTDI-Pad38)") (class "Default")
      (node (ref "IC3") (pin "38") (pinfunction "PA15/JTDI_38") (pintype "bidirectional"))
    )
    (net (code "67") (name "unconnected-(IC3-PB0{slash}ADC12_IN8{slash}TIM3_CH3-Pad18)") (class "Default")
      (node (ref "IC3") (pin "18") (pinfunction "PB0/ADC12_IN8/TIM3_CH3_18") (pintype "bidirectional"))
    )
    (net (code "68") (name "unconnected-(IC3-PB1{slash}ADC12_IN9{slash}TIM3_CH4-Pad19)") (class "Default")
      (node (ref "IC3") (pin "19") (pinfunction "PB1/ADC12_IN9/TIM3_CH4_19") (pintype "bidirectional"))
    )
    (net (code "69") (name "unconnected-(IC3-PB4{slash}JNTRST-Pad40)") (class "Default")
      (node (ref "IC3") (pin "40") (pinfunction "PB4/JNTRST_40") (pintype "bidirectional"))
    )
    (net (code "70") (name "unconnected-(IC3-PB5{slash}I2C1_SMBAI-Pad41)") (class "Default")
      (node (ref "IC3") (pin "41") (pinfunction "PB5/I2C1_SMBAI_41") (pintype "bidirectional"))
    )
    (net (code "71") (name "unconnected-(IC3-PB8{slash}TIM4_CH3-Pad45)") (class "Default")
      (node (ref "IC3") (pin "45") (pinfunction "PB8/TIM4_CH3_45") (pintype "bidirectional"))
    )
    (net (code "72") (name "unconnected-(IC3-PB9{slash}TIM4_CH4-Pad46)") (class "Default")
      (node (ref "IC3") (pin "46") (pinfunction "PB9/TIM4_CH4_46") (pintype "bidirectional"))
    )
    (net (code "73") (name "unconnected-(IC3-PC13_TAMPER_RTC-Pad2)") (class "Default")
      (node (ref "IC3") (pin "2") (pinfunction "PC13_TAMPER_RTC_2") (pintype "bidirectional"))
    )
    (net (code "74") (name "unconnected-(IC3-PC14-OSC32_IN-Pad3)") (class "Default")
      (node (ref "IC3") (pin "3") (pinfunction "PC14-OSC32_IN_3") (pintype "bidirectional"))
    )
    (net (code "75") (name "unconnected-(IC3-PC15_OSC32_OUT-Pad4)") (class "Default")
      (node (ref "IC3") (pin "4") (pinfunction "PC15_OSC32_OUT_4") (pintype "bidirectional"))
    )
    (net (code "76") (name "unconnected-(IC3-VBAT-Pad1)") (class "Default")
      (node (ref "IC3") (pin "1") (pinfunction "VBAT_1") (pintype "bidirectional"))
    )
  )
)
